# Desk_Clock_v1_0.net
KiCad netlist of a schematic drawn in EAGLE
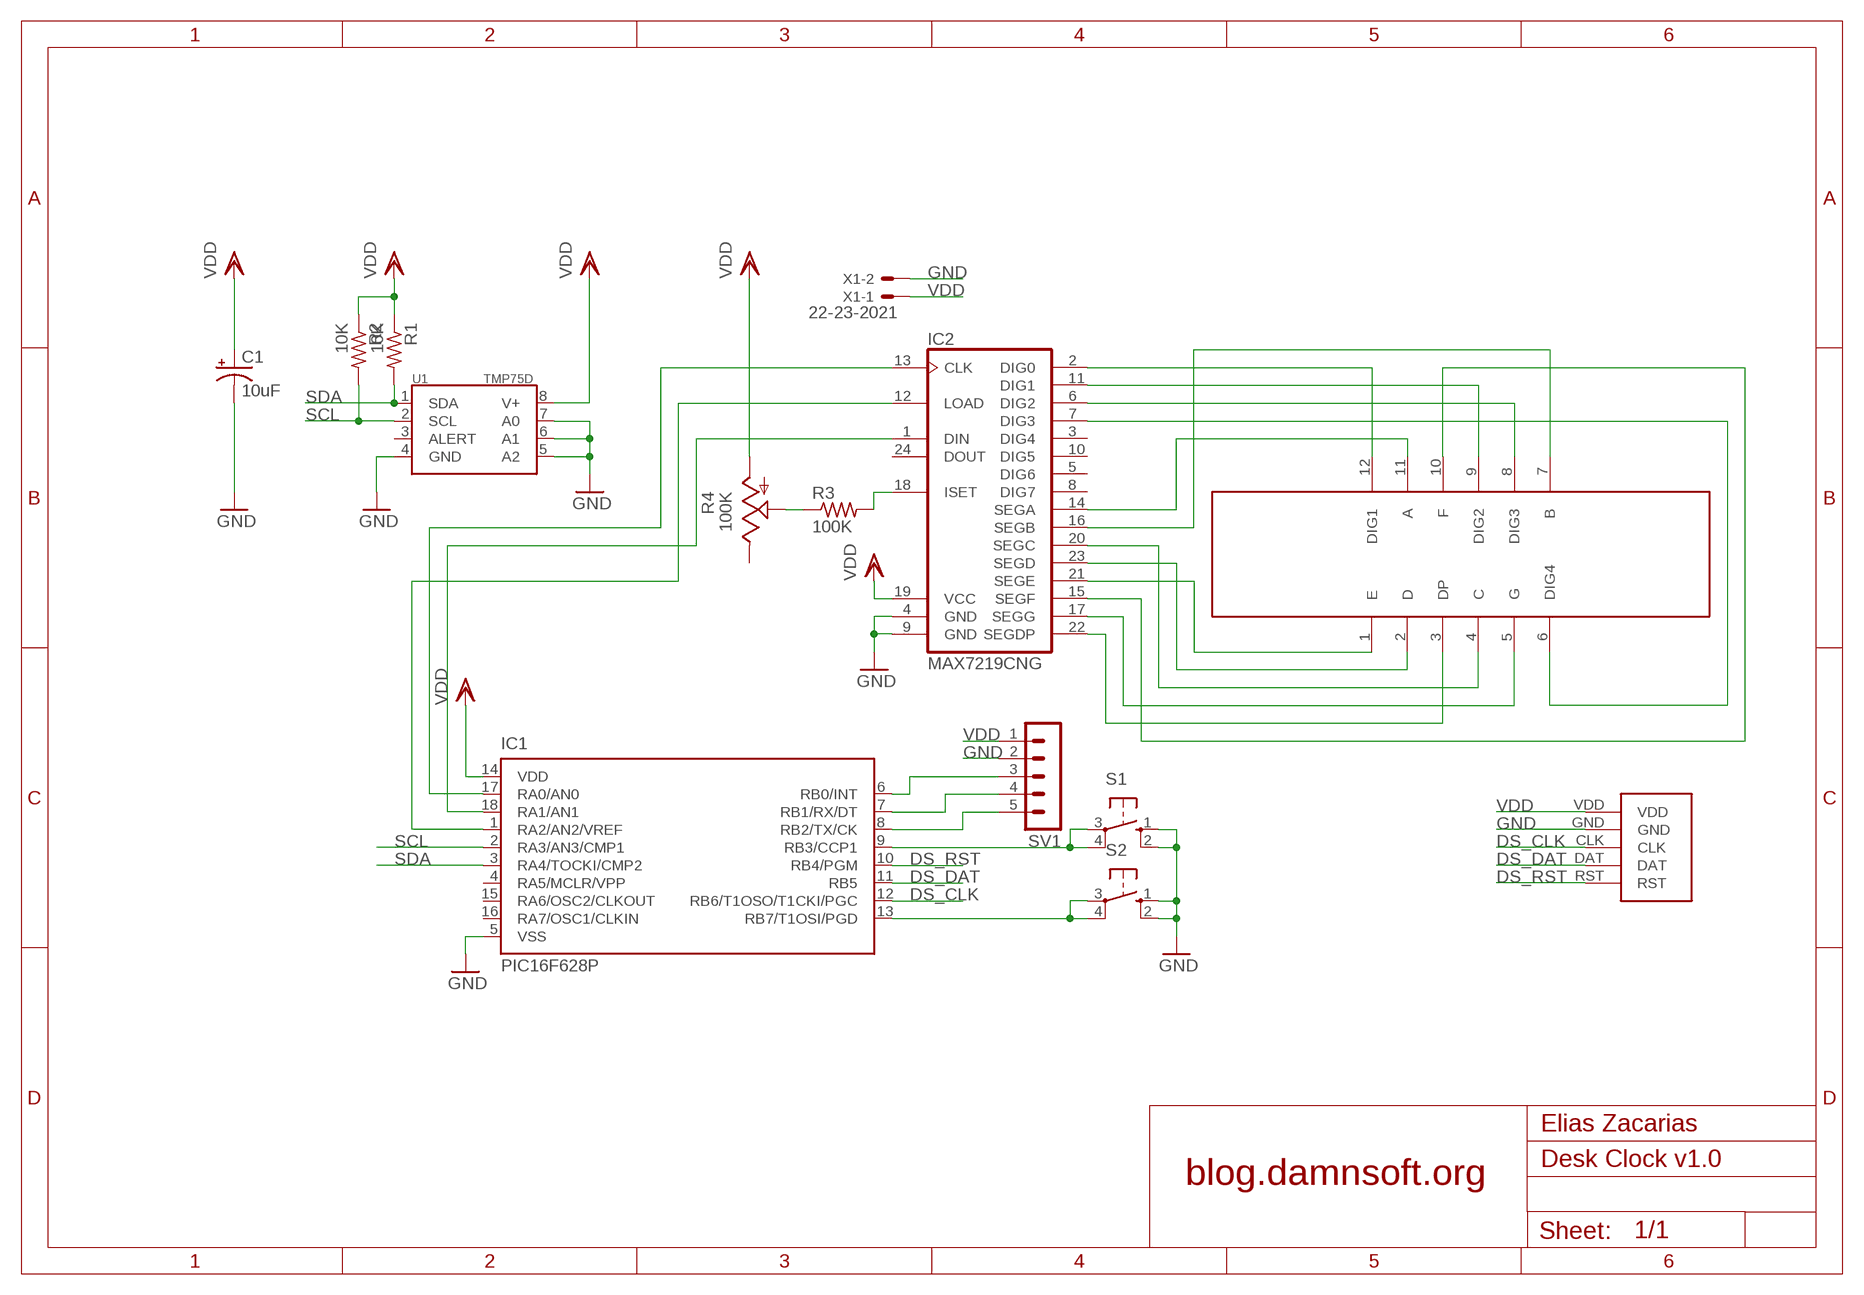
[diagram p0: schematic, sheet 1]

(export (version "E")
  (design (tool "Eeschema 10.0.6"))
  (components
    (comp (ref "C1")
      (value "10uF")
      (footprint "eagle-import:E2-4")
      (libsource (lib "eagle-import") (part "CPOL-USE2-4"))
    )
    (comp (ref "IC1")
      (value "PIC16F628P")
      (footprint "eagle-import:DIL18")
      (fields (field (name "MF") "MICROCHIP") (field (name "MPN") "PIC16F628-04I/P"))
      (libsource (lib "eagle-import") (part "PIC16F62P8"))
    )
    (comp (ref "IC2")
      (value "MAX7219CNG")
      (footprint "eagle-import:DIL24-3")
      (fields (field (name "MF") "MAXIM"))
      (libsource (lib "eagle-import") (part "MAX7219CNG"))
    )
    (comp (ref "R1")
      (value "10K")
      (footprint "eagle-import:0207_10")
      (libsource (lib "eagle-import") (part "R-US_0207/10"))
    )
    (comp (ref "R2")
      (value "10K")
      (footprint "eagle-import:0207_10")
      (libsource (lib "eagle-import") (part "R-US_0207/10"))
    )
    (comp (ref "R3")
      (value "100K")
      (footprint "eagle-import:0207_10")
      (libsource (lib "eagle-import") (part "R-US_0207/10"))
    )
    (comp (ref "R4")
      (value "100K")
      (footprint "eagle-import:CA6V")
      (libsource (lib "eagle-import") (part "TRIM_US-CA6V"))
    )
    (comp (ref "S1")
      (value "10-XX")
      (footprint "eagle-import:B3F-10XX")
      (fields (field (name "MPN") "B3F-1000"))
      (libsource (lib "eagle-import") (part "10-XX"))
    )
    (comp (ref "S2")
      (value "10-XX")
      (footprint "eagle-import:B3F-10XX")
      (fields (field (name "MPN") "B3F-1000"))
      (libsource (lib "eagle-import") (part "10-XX"))
    )
    (comp (ref "SV1")
      (value "MA05-1")
      (footprint "eagle-import:MA05-1")
      (libsource (lib "eagle-import") (part "MA05-1"))
    )
    (comp (ref "U$1")
      (value "NFD-5642BX")
      (footprint "eagle-import:DISPLAY")
      (libsource (lib "eagle-import") (part "NFD-5642BX"))
    )
    (comp (ref "U$2")
      (value "DS1302_BOARD")
      (footprint "eagle-import:DS1302_BOARD")
      (libsource (lib "eagle-import") (part "DS1302_BOARD"))
    )
    (comp (ref "U1")
      (value "TMP75D")
      (footprint "eagle-import:SO-08")
      (libsource (lib "eagle-import") (part "TMP75D"))
    )
    (comp (ref "X1")
      (value "22-23-2021")
      (footprint "eagle-import:22-23-2021")
      (fields (field (name "MF") "MOLEX"))
      (libsource (lib "eagle-import") (part "22-23-2021"))
    )
  )
  (nets
    (net (code "1") (name "/DS_CLK") (class "Default")
      (node (ref "IC1") (pin "12") (pinfunction "RB6/T1OSO/T1CKI/PGC_12") (pintype "bidirectional"))
      (node (ref "U$2") (pin "CLK") (pinfunction "CLK_CLK") (pintype "bidirectional"))
    )
    (net (code "2") (name "/DS_DAT") (class "Default")
      (node (ref "IC1") (pin "11") (pinfunction "RB5_11") (pintype "bidirectional"))
      (node (ref "U$2") (pin "DAT") (pinfunction "DAT_DAT") (pintype "bidirectional"))
    )
    (net (code "3") (name "/DS_RST") (class "Default")
      (node (ref "IC1") (pin "10") (pinfunction "RB4/PGM_10") (pintype "bidirectional"))
      (node (ref "U$2") (pin "RST") (pinfunction "RST_RST") (pintype "bidirectional"))
    )
    (net (code "4") (name "/SCL") (class "Default")
      (node (ref "IC1") (pin "2") (pinfunction "RA3/AN3/CMP1_2") (pintype "bidirectional"))
      (node (ref "R2") (pin "2") (pinfunction "2_2") (pintype "passive"))
      (node (ref "U1") (pin "2") (pinfunction "SCL_2") (pintype "bidirectional"))
    )
    (net (code "5") (name "/SDA") (class "Default")
      (node (ref "IC1") (pin "3") (pinfunction "RA4/TOCKI/CMP2_3") (pintype "bidirectional"))
      (node (ref "R1") (pin "2") (pinfunction "2_2") (pintype "passive"))
      (node (ref "U1") (pin "1") (pinfunction "SDA_1") (pintype "bidirectional"))
    )
    (net (code "6") (name "GND") (class "Default")
      (node (ref "C1") (pin "-") (pinfunction "-_-") (pintype "passive"))
      (node (ref "IC1") (pin "5") (pinfunction "VSS_5") (pintype "power_in"))
      (node (ref "IC2") (pin "4") (pinfunction "GND_4") (pintype "power_in"))
      (node (ref "IC2") (pin "9") (pinfunction "GND_9") (pintype "power_in"))
      (node (ref "S1") (pin "1") (pinfunction "S_1") (pintype "passive"))
      (node (ref "S1") (pin "2") (pinfunction "S1_2") (pintype "passive"))
      (node (ref "S2") (pin "1") (pinfunction "S_1") (pintype "passive"))
      (node (ref "S2") (pin "2") (pinfunction "S1_2") (pintype "passive"))
      (node (ref "SV1") (pin "2") (pinfunction "2_2") (pintype "passive"))
      (node (ref "U$2") (pin "GND") (pinfunction "GND_GND") (pintype "bidirectional"))
      (node (ref "U1") (pin "4") (pinfunction "GND_4") (pintype "bidirectional"))
      (node (ref "U1") (pin "5") (pinfunction "A2_5") (pintype "bidirectional"))
      (node (ref "U1") (pin "6") (pinfunction "A1_6") (pintype "bidirectional"))
      (node (ref "U1") (pin "7") (pinfunction "A0_7") (pintype "bidirectional"))
      (node (ref "X1") (pin "2") (pinfunction "S_2") (pintype "passive"))
    )
    (net (code "7") (name "Net-(IC1-RA0{slash}AN0)") (class "Default")
      (node (ref "IC1") (pin "17") (pinfunction "RA0/AN0_17") (pintype "bidirectional"))
      (node (ref "IC2") (pin "13") (pinfunction "CLK_13") (pintype "input"))
    )
    (net (code "8") (name "Net-(IC1-RA1{slash}AN1)") (class "Default")
      (node (ref "IC1") (pin "18") (pinfunction "RA1/AN1_18") (pintype "bidirectional"))
      (node (ref "IC2") (pin "1") (pinfunction "DIN_1") (pintype "input"))
    )
    (net (code "9") (name "Net-(IC1-RA2{slash}AN2{slash}VREF)") (class "Default")
      (node (ref "IC1") (pin "1") (pinfunction "RA2/AN2/VREF_1") (pintype "bidirectional"))
      (node (ref "IC2") (pin "12") (pinfunction "LOAD_12") (pintype "input"))
    )
    (net (code "10") (name "Net-(IC1-RB0{slash}INT)") (class "Default")
      (node (ref "IC1") (pin "6") (pinfunction "RB0/INT_6") (pintype "bidirectional"))
      (node (ref "SV1") (pin "3") (pinfunction "3_3") (pintype "passive"))
    )
    (net (code "11") (name "Net-(IC1-RB1{slash}RX{slash}DT)") (class "Default")
      (node (ref "IC1") (pin "7") (pinfunction "RB1/RX/DT_7") (pintype "bidirectional"))
      (node (ref "SV1") (pin "4") (pinfunction "4_4") (pintype "passive"))
    )
    (net (code "12") (name "Net-(IC1-RB2{slash}TX{slash}CK)") (class "Default")
      (node (ref "IC1") (pin "8") (pinfunction "RB2/TX/CK_8") (pintype "bidirectional"))
      (node (ref "SV1") (pin "5") (pinfunction "5_5") (pintype "passive"))
    )
    (net (code "13") (name "Net-(IC1-RB3{slash}CCP1)") (class "Default")
      (node (ref "IC1") (pin "9") (pinfunction "RB3/CCP1_9") (pintype "bidirectional"))
      (node (ref "S1") (pin "3") (pinfunction "P_3") (pintype "passive"))
      (node (ref "S1") (pin "4") (pinfunction "P1_4") (pintype "passive"))
    )
    (net (code "14") (name "Net-(IC1-RB7{slash}T1OSI{slash}PGD)") (class "Default")
      (node (ref "IC1") (pin "13") (pinfunction "RB7/T1OSI/PGD_13") (pintype "bidirectional"))
      (node (ref "S2") (pin "3") (pinfunction "P_3") (pintype "passive"))
      (node (ref "S2") (pin "4") (pinfunction "P1_4") (pintype "passive"))
    )
    (net (code "15") (name "Net-(IC2-DIG0)") (class "Default")
      (node (ref "IC2") (pin "2") (pinfunction "DIG0_2") (pintype "output"))
      (node (ref "U$1") (pin "12") (pinfunction "DIG1_12") (pintype "bidirectional"))
    )
    (net (code "16") (name "Net-(IC2-DIG1)") (class "Default")
      (node (ref "IC2") (pin "11") (pinfunction "DIG1_11") (pintype "output"))
      (node (ref "U$1") (pin "9") (pinfunction "DIG2_9") (pintype "bidirectional"))
    )
    (net (code "17") (name "Net-(IC2-DIG2)") (class "Default")
      (node (ref "IC2") (pin "6") (pinfunction "DIG2_6") (pintype "output"))
      (node (ref "U$1") (pin "8") (pinfunction "DIG3_8") (pintype "bidirectional"))
    )
    (net (code "18") (name "Net-(IC2-DIG3)") (class "Default")
      (node (ref "IC2") (pin "7") (pinfunction "DIG3_7") (pintype "output"))
      (node (ref "U$1") (pin "6") (pinfunction "DIG4_6") (pintype "bidirectional"))
    )
    (net (code "19") (name "Net-(IC2-ISET)") (class "Default")
      (node (ref "IC2") (pin "18") (pinfunction "ISET_18") (pintype "input"))
      (node (ref "R3") (pin "2") (pinfunction "2_2") (pintype "passive"))
    )
    (net (code "20") (name "Net-(IC2-SEGA)") (class "Default")
      (node (ref "IC2") (pin "14") (pinfunction "SEGA_14") (pintype "output"))
      (node (ref "U$1") (pin "11") (pinfunction "A_11") (pintype "bidirectional"))
    )
    (net (code "21") (name "Net-(IC2-SEGB)") (class "Default")
      (node (ref "IC2") (pin "16") (pinfunction "SEGB_16") (pintype "output"))
      (node (ref "U$1") (pin "7") (pinfunction "B_7") (pintype "bidirectional"))
    )
    (net (code "22") (name "Net-(IC2-SEGC)") (class "Default")
      (node (ref "IC2") (pin "20") (pinfunction "SEGC_20") (pintype "output"))
      (node (ref "U$1") (pin "4") (pinfunction "C_4") (pintype "bidirectional"))
    )
    (net (code "23") (name "Net-(IC2-SEGD)") (class "Default")
      (node (ref "IC2") (pin "23") (pinfunction "SEGD_23") (pintype "output"))
      (node (ref "U$1") (pin "2") (pinfunction "D_2") (pintype "bidirectional"))
    )
    (net (code "24") (name "Net-(IC2-SEGDP)") (class "Default")
      (node (ref "IC2") (pin "22") (pinfunction "SEGDP_22") (pintype "output"))
      (node (ref "U$1") (pin "3") (pinfunction "DP_3") (pintype "bidirectional"))
    )
    (net (code "25") (name "Net-(IC2-SEGE)") (class "Default")
      (node (ref "IC2") (pin "21") (pinfunction "SEGE_21") (pintype "output"))
      (node (ref "U$1") (pin "1") (pinfunction "E_1") (pintype "bidirectional"))
    )
    (net (code "26") (name "Net-(IC2-SEGF)") (class "Default")
      (node (ref "IC2") (pin "15") (pinfunction "SEGF_15") (pintype "output"))
      (node (ref "U$1") (pin "10") (pinfunction "F_10") (pintype "bidirectional"))
    )
    (net (code "27") (name "Net-(IC2-SEGG)") (class "Default")
      (node (ref "IC2") (pin "17") (pinfunction "SEGG_17") (pintype "output"))
      (node (ref "U$1") (pin "5") (pinfunction "G_5") (pintype "bidirectional"))
    )
    (net (code "28") (name "Net-(R3-Pad1)") (class "Default")
      (node (ref "R3") (pin "1") (pinfunction "1_1") (pintype "passive"))
      (node (ref "R4") (pin "S") (pinfunction "S_S") (pintype "passive"))
    )
    (net (code "29") (name "VDD") (class "Default")
      (node (ref "C1") (pin "+") (pinfunction "+_+") (pintype "passive"))
      (node (ref "IC1") (pin "14") (pinfunction "VDD_14") (pintype "power_in"))
      (node (ref "IC2") (pin "19") (pinfunction "VCC_19") (pintype "power_in"))
      (node (ref "R1") (pin "1") (pinfunction "1_1") (pintype "passive"))
      (node (ref "R2") (pin "1") (pinfunction "1_1") (pintype "passive"))
      (node (ref "R4") (pin "A") (pinfunction "A_A") (pintype "passive"))
      (node (ref "SV1") (pin "1") (pinfunction "1_1") (pintype "passive"))
      (node (ref "U$2") (pin "VDD") (pinfunction "VDD_VDD") (pintype "bidirectional"))
      (node (ref "U1") (pin "8") (pinfunction "V+_8") (pintype "bidirectional"))
      (node (ref "X1") (pin "1") (pinfunction "S_1") (pintype "passive"))
    )
    (net (code "30") (name "unconnected-(IC1-RA5{slash}MCLR{slash}VPP-Pad4)") (class "Default")
      (node (ref "IC1") (pin "4") (pinfunction "RA5/MCLR/VPP_4") (pintype "bidirectional"))
    )
    (net (code "31") (name "unconnected-(IC1-RA6{slash}OSC2{slash}CLKOUT-Pad15)") (class "Default")
      (node (ref "IC1") (pin "15") (pinfunction "RA6/OSC2/CLKOUT_15") (pintype "bidirectional"))
    )
    (net (code "32") (name "unconnected-(IC1-RA7{slash}OSC1{slash}CLKIN-Pad16)") (class "Default")
      (node (ref "IC1") (pin "16") (pinfunction "RA7/OSC1/CLKIN_16") (pintype "bidirectional"))
    )
    (net (code "33") (name "unconnected-(IC2-DIG4-Pad3)") (class "Default")
      (node (ref "IC2") (pin "3") (pinfunction "DIG4_3") (pintype "output"))
    )
    (net (code "34") (name "unconnected-(IC2-DIG5-Pad10)") (class "Default")
      (node (ref "IC2") (pin "10") (pinfunction "DIG5_10") (pintype "output"))
    )
    (net (code "35") (name "unconnected-(IC2-DIG6-Pad5)") (class "Default")
      (node (ref "IC2") (pin "5") (pinfunction "DIG6_5") (pintype "output"))
    )
    (net (code "36") (name "unconnected-(IC2-DIG7-Pad8)") (class "Default")
      (node (ref "IC2") (pin "8") (pinfunction "DIG7_8") (pintype "output"))
    )
    (net (code "37") (name "unconnected-(IC2-DOUT-Pad24)") (class "Default")
      (node (ref "IC2") (pin "24") (pinfunction "DOUT_24") (pintype "output"))
    )
    (net (code "38") (name "unconnected-(R4-PadE)") (class "Default")
      (node (ref "R4") (pin "E") (pinfunction "E_E") (pintype "passive"))
    )
    (net (code "39") (name "unconnected-(U1-ALERT-Pad3)") (class "Default")
      (node (ref "U1") (pin "3") (pinfunction "ALERT_3") (pintype "bidirectional"))
    )
  )
)
